# Linear_VCA_chip_v1_1.net
KiCad netlist of a schematic drawn in EAGLE
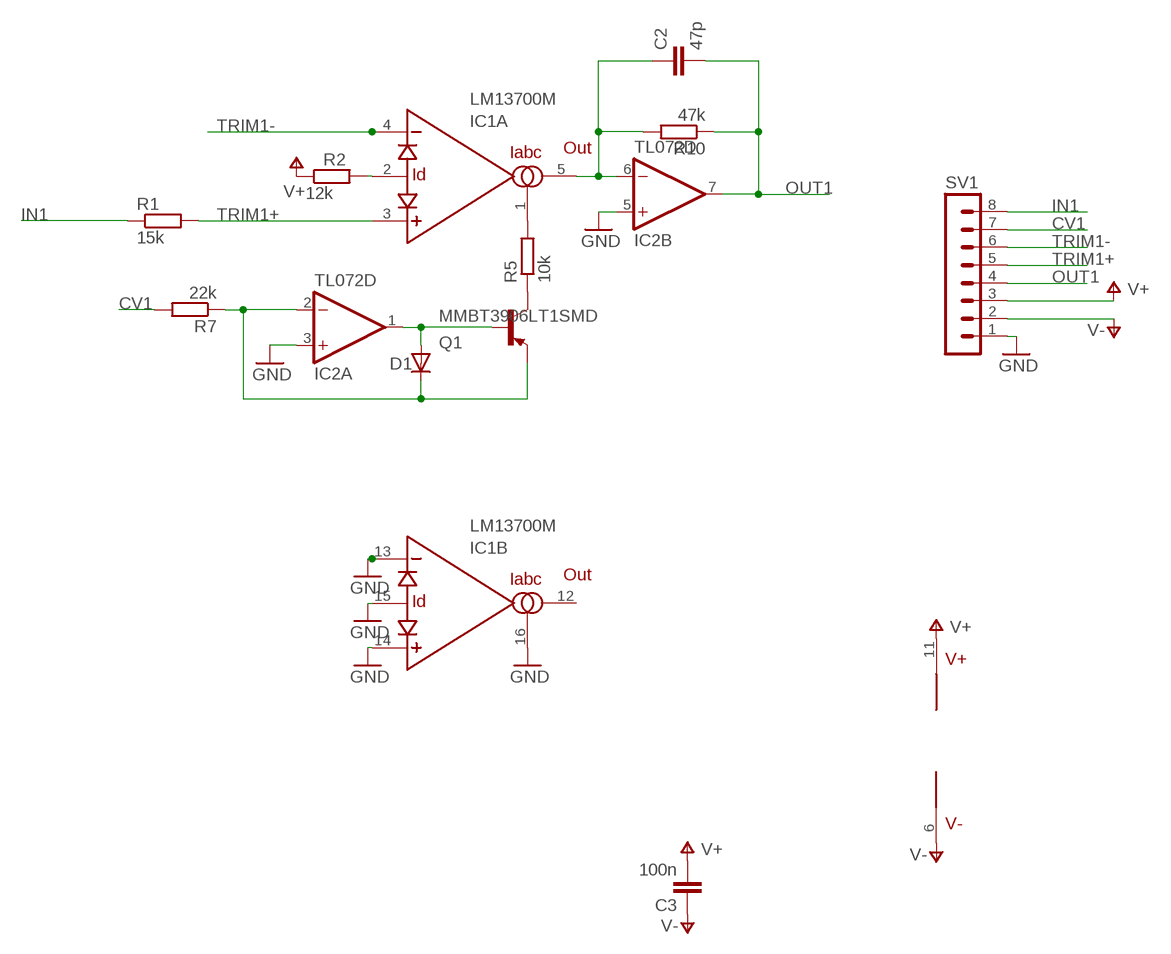
[diagram p0: schematic, sheet 1]

(export (version "E")
  (design (tool "Eeschema 10.0.6"))
  (components
    (comp (ref "C2")
      (value "47p")
      (footprint "eagle-import:C0805")
      (libsource (lib "eagle-import") (part "C-EUC0805"))
    )
    (comp (ref "C3")
      (value "100n")
      (footprint "eagle-import:C0805")
      (libsource (lib "eagle-import") (part "C-EUC0805"))
    )
    (comp (ref "D1")
      (value "DIODE-SOD80C")
      (footprint "eagle-import:SOD80C")
      (libsource (lib "eagle-import") (part "DIODE-SOD80C"))
    )
    (comp (ref "IC1")
      (value "LM13700M")
      (footprint "eagle-import:SO16")
      (libsource (lib "eagle-import") (part "LM13700M"))
    )
    (comp (ref "IC2")
      (value "TL072D")
      (footprint "eagle-import:SO08")
      (libsource (lib "eagle-import") (part "TL072D"))
    )
    (comp (ref "Q1")
      (value "MMBT3906LT1SMD")
      (footprint "eagle-import:SOT23-BEC")
      (libsource (lib "eagle-import") (part "MMBT3906SMDLT1"))
    )
    (comp (ref "R1")
      (value "15k")
      (footprint "eagle-import:R0805")
      (libsource (lib "eagle-import") (part "R-EU_R0805"))
    )
    (comp (ref "R2")
      (value "12k")
      (footprint "eagle-import:R0805")
      (libsource (lib "eagle-import") (part "R-EU_R0805"))
    )
    (comp (ref "R5")
      (value "10k")
      (footprint "eagle-import:R0805")
      (libsource (lib "eagle-import") (part "R-EU_R0805"))
    )
    (comp (ref "R7")
      (value "22k")
      (footprint "eagle-import:R0805")
      (libsource (lib "eagle-import") (part "R-EU_R0805"))
    )
    (comp (ref "R10")
      (value "47k")
      (footprint "eagle-import:R0805")
      (libsource (lib "eagle-import") (part "R-EU_R0805"))
    )
    (comp (ref "SV1")
      (value "MA08-1")
      (footprint "eagle-import:MA08-1")
      (libsource (lib "eagle-import") (part "MA08-1"))
    )
  )
  (nets
    (net (code "1") (name "/CV1") (class "Default")
      (node (ref "R7") (pin "2") (pinfunction "2_2") (pintype "passive"))
      (node (ref "SV1") (pin "7") (pinfunction "7_7") (pintype "passive"))
    )
    (net (code "2") (name "/IN1") (class "Default")
      (node (ref "R1") (pin "1") (pinfunction "1_1") (pintype "passive"))
      (node (ref "SV1") (pin "8") (pinfunction "8_8") (pintype "passive"))
    )
    (net (code "3") (name "/OUT1") (class "Default")
      (node (ref "C2") (pin "2") (pinfunction "2_2") (pintype "passive"))
      (node (ref "IC2") (pin "7") (pinfunction "OUT_7") (pintype "output"))
      (node (ref "R10") (pin "1") (pinfunction "1_1") (pintype "passive"))
      (node (ref "SV1") (pin "4") (pinfunction "4_4") (pintype "passive"))
    )
    (net (code "4") (name "/TRIM1+") (class "Default")
      (node (ref "IC1") (pin "3") (pinfunction "+IN_3") (pintype "bidirectional"))
      (node (ref "R1") (pin "2") (pinfunction "2_2") (pintype "passive"))
      (node (ref "SV1") (pin "5") (pinfunction "5_5") (pintype "passive"))
    )
    (net (code "5") (name "/TRIM1-") (class "Default")
      (node (ref "IC1") (pin "4") (pinfunction "-IN_4") (pintype "bidirectional"))
      (node (ref "SV1") (pin "6") (pinfunction "6_6") (pintype "passive"))
    )
    (net (code "6") (name "GND") (class "Default")
      (node (ref "IC1") (pin "13") (pinfunction "-IN_13") (pintype "bidirectional"))
      (node (ref "IC1") (pin "14") (pinfunction "+IN_14") (pintype "bidirectional"))
      (node (ref "IC1") (pin "15") (pinfunction "ID_15") (pintype "bidirectional"))
      (node (ref "IC1") (pin "16") (pinfunction "IABC_16") (pintype "bidirectional"))
      (node (ref "IC2") (pin "3") (pinfunction "+IN_3") (pintype "input"))
      (node (ref "IC2") (pin "5") (pinfunction "+IN_5") (pintype "input"))
      (node (ref "SV1") (pin "1") (pinfunction "1_1") (pintype "passive"))
    )
    (net (code "7") (name "Net-(IC1A-IABC)") (class "Default")
      (node (ref "IC1") (pin "1") (pinfunction "IABC_1") (pintype "bidirectional"))
      (node (ref "R5") (pin "2") (pinfunction "2_2") (pintype "passive"))
    )
    (net (code "8") (name "Net-(IC1A-ID)") (class "Default")
      (node (ref "IC1") (pin "2") (pinfunction "ID_2") (pintype "bidirectional"))
      (node (ref "R2") (pin "2") (pinfunction "2_2") (pintype "passive"))
    )
    (net (code "9") (name "Net-(IC1A-OUT)") (class "Default")
      (node (ref "C2") (pin "1") (pinfunction "1_1") (pintype "passive"))
      (node (ref "IC1") (pin "5") (pinfunction "OUT_5") (pintype "bidirectional"))
      (node (ref "IC2") (pin "6") (pinfunction "-IN_6") (pintype "input"))
      (node (ref "R10") (pin "2") (pinfunction "2_2") (pintype "passive"))
    )
    (net (code "10") (name "Net-(IC2A--IN)") (class "Default")
      (node (ref "D1") (pin "C") (pinfunction "C_C") (pintype "passive"))
      (node (ref "IC2") (pin "2") (pinfunction "-IN_2") (pintype "input"))
      (node (ref "Q1") (pin "E") (pinfunction "E_E") (pintype "passive"))
      (node (ref "R7") (pin "1") (pinfunction "1_1") (pintype "passive"))
    )
    (net (code "11") (name "Net-(IC2A-OUT)") (class "Default")
      (node (ref "D1") (pin "A") (pinfunction "A_A") (pintype "passive"))
      (node (ref "IC2") (pin "1") (pinfunction "OUT_1") (pintype "output"))
      (node (ref "Q1") (pin "B") (pinfunction "B_B") (pintype "passive"))
    )
    (net (code "12") (name "Net-(Q1-PadC)") (class "Default")
      (node (ref "Q1") (pin "C") (pinfunction "C_C") (pintype "passive"))
      (node (ref "R5") (pin "1") (pinfunction "1_1") (pintype "passive"))
    )
    (net (code "13") (name "V+") (class "Default")
      (node (ref "C3") (pin "2") (pinfunction "2_2") (pintype "passive"))
      (node (ref "IC1") (pin "11") (pinfunction "V+_11") (pintype "bidirectional"))
      (node (ref "R2") (pin "1") (pinfunction "1_1") (pintype "passive"))
      (node (ref "SV1") (pin "3") (pinfunction "3_3") (pintype "passive"))
    )
    (net (code "14") (name "V-") (class "Default")
      (node (ref "C3") (pin "1") (pinfunction "1_1") (pintype "passive"))
      (node (ref "IC1") (pin "6") (pinfunction "V-_6") (pintype "bidirectional"))
      (node (ref "SV1") (pin "2") (pinfunction "2_2") (pintype "passive"))
    )
    (net (code "15") (name "unconnected-(IC1B-OUT-Pad12)") (class "Default")
      (node (ref "IC1") (pin "12") (pinfunction "OUT_12") (pintype "bidirectional"))
    )
  )
)
